# Controller_V1_1.net
KiCad netlist of a schematic drawn in EAGLE
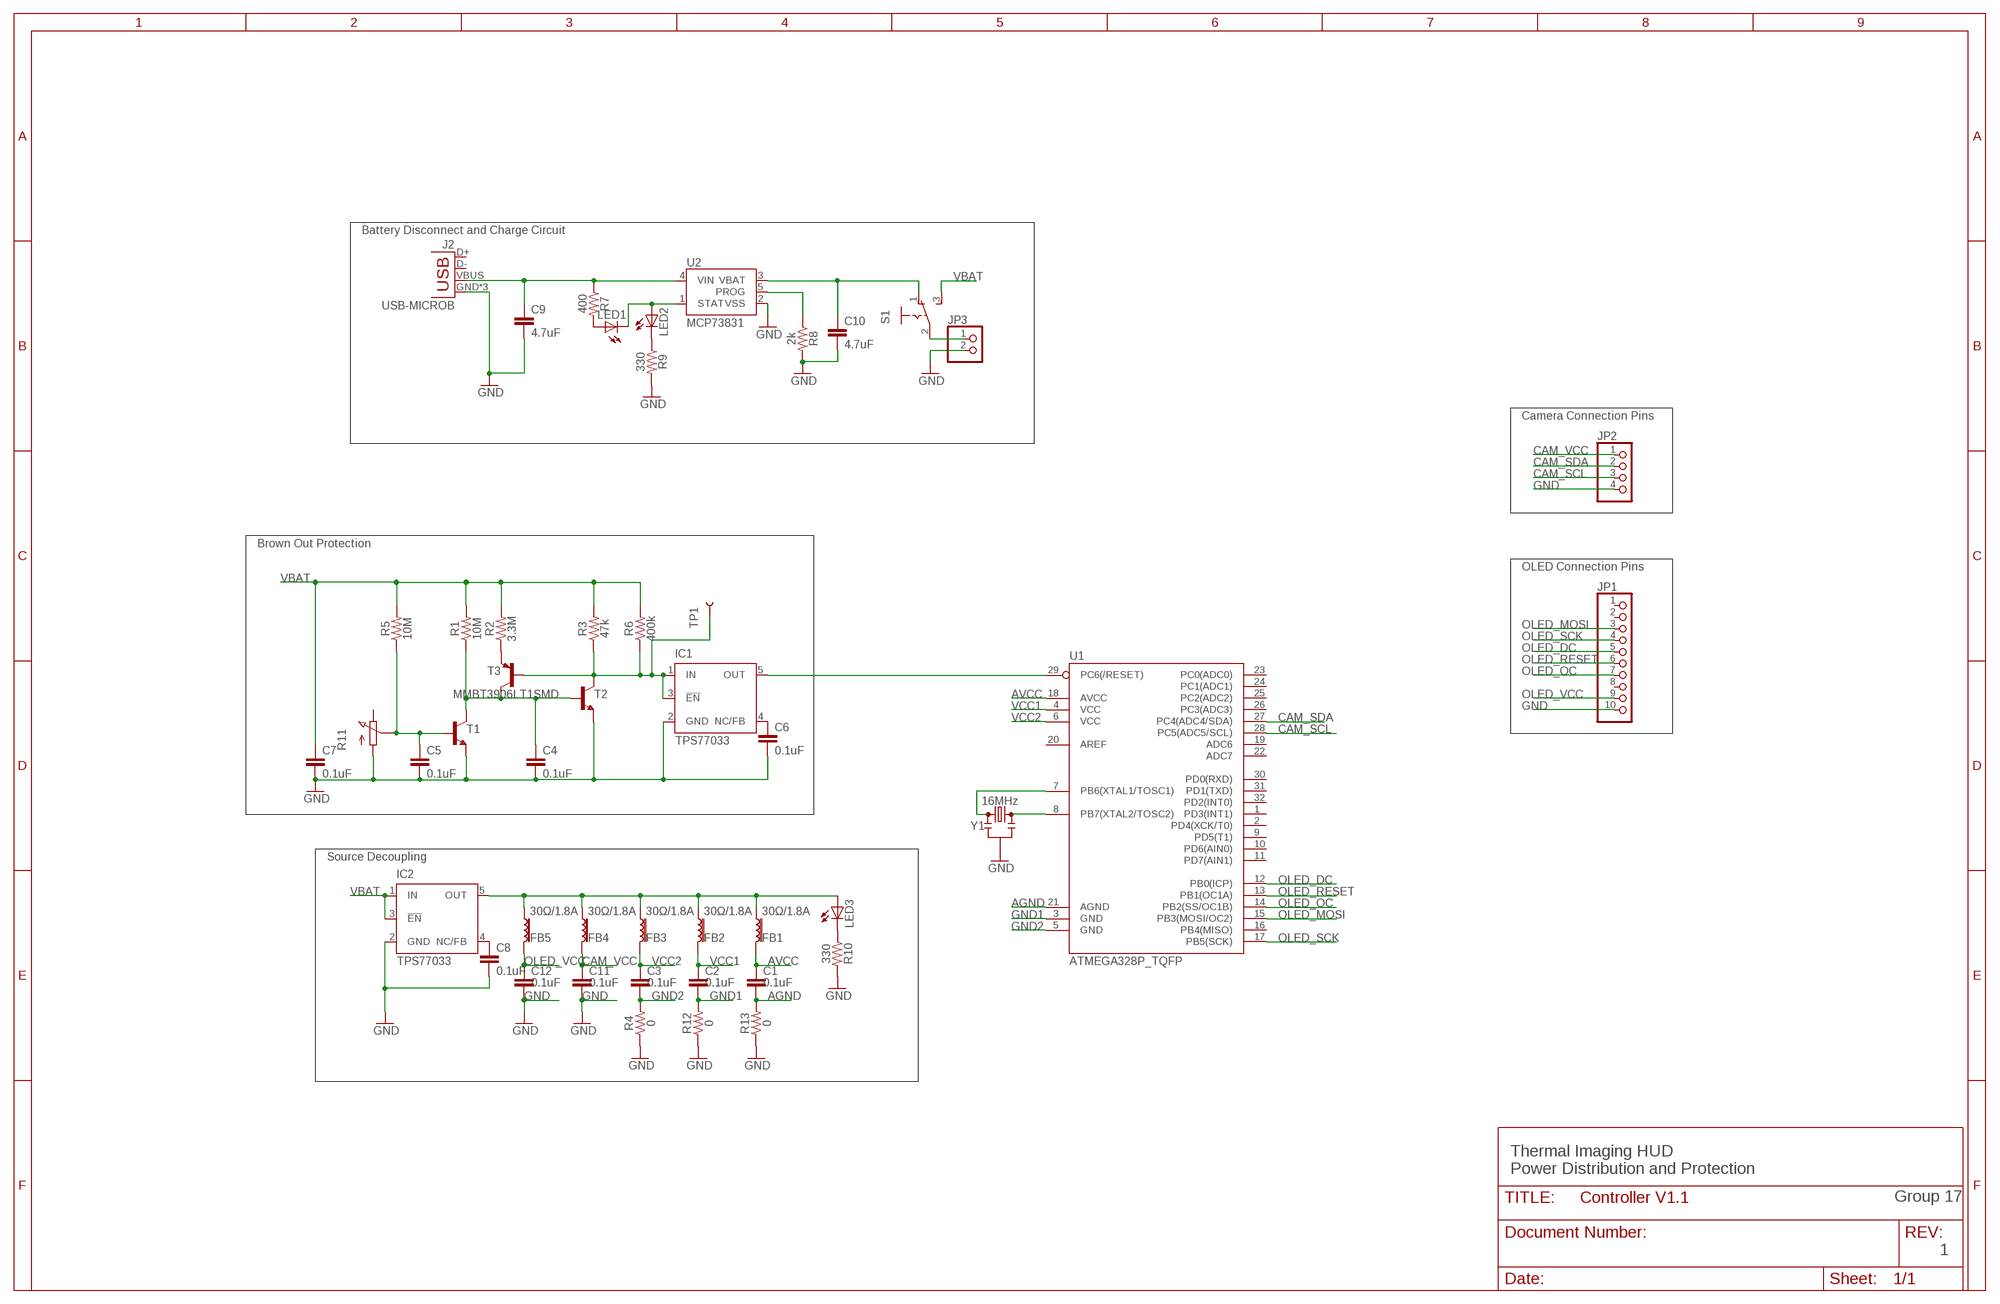
[diagram p0: schematic, sheet 1]

(export (version "E")
  (design (tool "Eeschema 10.0.6"))
  (components
    (comp (ref "C1")
      (value "0.1uF")
      (footprint "eagle-import:0603")
      (libsource (lib "eagle-import") (part "0.1UF-0603-25V-5%"))
    )
    (comp (ref "C2")
      (value "0.1uF")
      (footprint "eagle-import:0603")
      (libsource (lib "eagle-import") (part "0.1UF-0603-25V-5%"))
    )
    (comp (ref "C3")
      (value "0.1uF")
      (footprint "eagle-import:0603")
      (libsource (lib "eagle-import") (part "0.1UF-0603-25V-5%"))
    )
    (comp (ref "C4")
      (value "0.1uF")
      (footprint "eagle-import:0603")
      (libsource (lib "eagle-import") (part "0.1UF-0603-25V-5%"))
    )
    (comp (ref "C5")
      (value "0.1uF")
      (footprint "eagle-import:0603")
      (libsource (lib "eagle-import") (part "0.1UF-0603-25V-5%"))
    )
    (comp (ref "C6")
      (value "0.1uF")
      (footprint "eagle-import:0603")
      (libsource (lib "eagle-import") (part "0.1UF-0603-25V-5%"))
    )
    (comp (ref "C7")
      (value "0.1uF")
      (footprint "eagle-import:0603")
      (libsource (lib "eagle-import") (part "0.1UF-0603-25V-5%"))
    )
    (comp (ref "C8")
      (value "0.1uF")
      (footprint "eagle-import:0603")
      (libsource (lib "eagle-import") (part "0.1UF-0603-25V-5%"))
    )
    (comp (ref "C9")
      (value "4.7uF")
      (footprint "eagle-import:0603")
      (libsource (lib "eagle-import") (part "0.1UF-0603-25V-5%"))
    )
    (comp (ref "C10")
      (value "4.7uF")
      (footprint "eagle-import:0603")
      (libsource (lib "eagle-import") (part "0.1UF-0603-25V-5%"))
    )
    (comp (ref "C11")
      (value "0.1uF")
      (footprint "eagle-import:0603")
      (libsource (lib "eagle-import") (part "0.1UF-0603-25V-5%"))
    )
    (comp (ref "C12")
      (value "0.1uF")
      (footprint "eagle-import:0603")
      (libsource (lib "eagle-import") (part "0.1UF-0603-25V-5%"))
    )
    (comp (ref "FB1")
      (value "30Ω/1.8A")
      (footprint "eagle-import:0603")
      (libsource (lib "eagle-import") (part "FERRITE_BEAD-0603"))
    )
    (comp (ref "FB2")
      (value "30Ω/1.8A")
      (footprint "eagle-import:0603")
      (libsource (lib "eagle-import") (part "FERRITE_BEAD-0603"))
    )
    (comp (ref "FB3")
      (value "30Ω/1.8A")
      (footprint "eagle-import:0603")
      (libsource (lib "eagle-import") (part "FERRITE_BEAD-0603"))
    )
    (comp (ref "FB4")
      (value "30Ω/1.8A")
      (footprint "eagle-import:0603")
      (libsource (lib "eagle-import") (part "FERRITE_BEAD-0603"))
    )
    (comp (ref "FB5")
      (value "30Ω/1.8A")
      (footprint "eagle-import:0603")
      (libsource (lib "eagle-import") (part "FERRITE_BEAD-0603"))
    )
    (comp (ref "IC1")
      (value "TPS77033")
      (footprint "eagle-import:SOT23-DBV")
      (fields (field (name "MF") "TEXAS INSTRUMENTS") (field (name "MPN") "TPS77033DBVT"))
      (libsource (lib "eagle-import") (part "TPS77033"))
    )
    (comp (ref "IC2")
      (value "TPS77033")
      (footprint "eagle-import:SOT23-DBV")
      (fields (field (name "MF") "TEXAS INSTRUMENTS") (field (name "MPN") "TPS77033DBVT"))
      (libsource (lib "eagle-import") (part "TPS77033"))
    )
    (comp (ref "J2")
      (value "USB-MICROB")
      (footprint "eagle-import:USB-MICROB")
      (libsource (lib "eagle-import") (part "USB-MICROB"))
    )
    (comp (ref "JP1")
      (value "PINHD-1X10/90")
      (footprint "eagle-import:1X10_90")
      (libsource (lib "eagle-import") (part "PINHD-1X10/90"))
    )
    (comp (ref "JP2")
      (value "PINHD-1X4/90")
      (footprint "eagle-import:1X04_90")
      (libsource (lib "eagle-import") (part "PINHD-1X4/90"))
    )
    (comp (ref "JP3")
      (value "PINHD-1X2/90")
      (footprint "eagle-import:1X02_90")
      (libsource (lib "eagle-import") (part "PINHD-1X2/90"))
    )
    (comp (ref "LED1")
      (value "LS_T679-D2E2-1")
      (footprint "eagle-import:PLCC2")
      (libsource (lib "eagle-import") (part "_T679-?-1D2E2LS"))
    )
    (comp (ref "LED2")
      (value "LG_T679-E1F1-1")
      (footprint "eagle-import:PLCC2")
      (libsource (lib "eagle-import") (part "_T679-?-1E1F1LG"))
    )
    (comp (ref "LED3")
      (value "LG_T679-E1F1-1")
      (footprint "eagle-import:PLCC2")
      (libsource (lib "eagle-import") (part "_T679-?-1E1F1LG"))
    )
    (comp (ref "R1")
      (value "10M")
      (footprint "eagle-import:0603")
      (libsource (lib "eagle-import") (part "10MOHM-0603-1/10W-5%"))
    )
    (comp (ref "R2")
      (value "3.3M")
      (footprint "eagle-import:0603")
      (libsource (lib "eagle-import") (part "10MOHM-0603-1/10W-5%"))
    )
    (comp (ref "R3")
      (value "47k")
      (footprint "eagle-import:0603")
      (libsource (lib "eagle-import") (part "10MOHM-0603-1/10W-5%"))
    )
    (comp (ref "R4")
      (value "0")
      (footprint "eagle-import:0603")
      (libsource (lib "eagle-import") (part "0OHM-0603-1/10W-5%"))
    )
    (comp (ref "R5")
      (value "10M")
      (footprint "eagle-import:0603")
      (libsource (lib "eagle-import") (part "10MOHM-0603-1/10W-5%"))
    )
    (comp (ref "R6")
      (value "400k")
      (footprint "eagle-import:0603")
      (libsource (lib "eagle-import") (part "10MOHM-0603-1/10W-5%"))
    )
    (comp (ref "R7")
      (value "400")
      (footprint "eagle-import:0603")
      (libsource (lib "eagle-import") (part "10MOHM-0603-1/10W-5%"))
    )
    (comp (ref "R8")
      (value "2k")
      (footprint "eagle-import:0603")
      (libsource (lib "eagle-import") (part "10MOHM-0603-1/10W-5%"))
    )
    (comp (ref "R9")
      (value "330")
      (footprint "eagle-import:0603")
      (libsource (lib "eagle-import") (part "10MOHM-0603-1/10W-5%"))
    )
    (comp (ref "R10")
      (value "330")
      (footprint "eagle-import:0603")
      (libsource (lib "eagle-import") (part "10MOHM-0603-1/10W-5%"))
    )
    (comp (ref "R11")
      (value "PC25")
      (footprint "eagle-import:PC25")
      (fields (field (name "MF") "CLAROSTAT") (field (name "MPN") "308NPC25KS"))
      (libsource (lib "eagle-import") (part "PC25"))
    )
    (comp (ref "R12")
      (value "0")
      (footprint "eagle-import:0603")
      (libsource (lib "eagle-import") (part "0OHM-0603-1/10W-5%"))
    )
    (comp (ref "R13")
      (value "0")
      (footprint "eagle-import:0603")
      (libsource (lib "eagle-import") (part "0OHM-0603-1/10W-5%"))
    )
    (comp (ref "S1")
      (value "255SB")
      (footprint "eagle-import:255SB")
      (libsource (lib "eagle-import") (part "255SB"))
    )
    (comp (ref "T1")
      (value "MMBT3904LT1-NPN-SOT23-BEC")
      (footprint "eagle-import:SOT23-BEC")
      (libsource (lib "eagle-import") (part "-NPN-SOT23-BECMMBT3904LT1"))
    )
    (comp (ref "T2")
      (value "MMBT3904LT1-NPN-SOT23-BEC")
      (footprint "eagle-import:SOT23-BEC")
      (libsource (lib "eagle-import") (part "-NPN-SOT23-BECMMBT3904LT1"))
    )
    (comp (ref "T3")
      (value "MMBT3906LT1SMD")
      (footprint "eagle-import:SOT23-BEC")
      (libsource (lib "eagle-import") (part "MMBT3906SMDLT1"))
    )
    (comp (ref "TP1")
      (value "TEST-POINT3X5")
      (footprint "eagle-import:PAD.03X.05")
      (libsource (lib "eagle-import") (part "TEST-POINT3X5"))
    )
    (comp (ref "U1")
      (value "ATMEGA328P_TQFP")
      (footprint "eagle-import:TQFP32-08")
      (libsource (lib "eagle-import") (part "ATMEGA328P_TQFP"))
    )
    (comp (ref "U2")
      (value "MCP73831")
      (footprint "eagle-import:SOT23-5")
      (libsource (lib "eagle-import") (part "MCP73831"))
    )
    (comp (ref "Y1")
      (value "16MHz")
      (footprint "eagle-import:RESONATOR-SMD-3.2X1.3")
      (libsource (lib "eagle-import") (part "RESONATOR-16MHZSMD_3.2X1.3"))
    )
  )
  (nets
    (net (code "1") (name "/AGND") (class "Default")
      (node (ref "C1") (pin "2") (pinfunction "2_2") (pintype "passive"))
      (node (ref "R13") (pin "2") (pinfunction "2_2") (pintype "passive"))
      (node (ref "U1") (pin "21") (pinfunction "AGND_21") (pintype "bidirectional"))
    )
    (net (code "2") (name "/AVCC") (class "Default")
      (node (ref "C1") (pin "1") (pinfunction "1_1") (pintype "passive"))
      (node (ref "FB1") (pin "2") (pinfunction "2_2") (pintype "passive"))
      (node (ref "U1") (pin "18") (pinfunction "AVCC_18") (pintype "bidirectional"))
    )
    (net (code "3") (name "/CAM_SCL") (class "Default")
      (node (ref "JP2") (pin "3") (pinfunction "3_3") (pintype "passive"))
      (node (ref "U1") (pin "28") (pinfunction "PC5(ADC5/SCL)_28") (pintype "bidirectional"))
    )
    (net (code "4") (name "/CAM_SDA") (class "Default")
      (node (ref "JP2") (pin "2") (pinfunction "2_2") (pintype "passive"))
      (node (ref "U1") (pin "27") (pinfunction "PC4(ADC4/SDA)_27") (pintype "bidirectional"))
    )
    (net (code "5") (name "/CAM_VCC") (class "Default")
      (node (ref "C11") (pin "1") (pinfunction "1_1") (pintype "passive"))
      (node (ref "FB4") (pin "2") (pinfunction "2_2") (pintype "passive"))
      (node (ref "JP2") (pin "1") (pinfunction "1_1") (pintype "passive"))
    )
    (net (code "6") (name "/GND1") (class "Default")
      (node (ref "C2") (pin "2") (pinfunction "2_2") (pintype "passive"))
      (node (ref "R12") (pin "2") (pinfunction "2_2") (pintype "passive"))
      (node (ref "U1") (pin "3") (pinfunction "GND_3") (pintype "bidirectional"))
    )
    (net (code "7") (name "/GND2") (class "Default")
      (node (ref "C3") (pin "2") (pinfunction "2_2") (pintype "passive"))
      (node (ref "R4") (pin "2") (pinfunction "2_2") (pintype "passive"))
      (node (ref "U1") (pin "5") (pinfunction "GND_5") (pintype "bidirectional"))
    )
    (net (code "8") (name "/OLED_DC") (class "Default")
      (node (ref "JP1") (pin "5") (pinfunction "5_5") (pintype "passive"))
      (node (ref "U1") (pin "12") (pinfunction "PB0(ICP)_12") (pintype "bidirectional"))
    )
    (net (code "9") (name "/OLED_MOSI") (class "Default")
      (node (ref "JP1") (pin "3") (pinfunction "3_3") (pintype "passive"))
      (node (ref "U1") (pin "15") (pinfunction "PB3(MOSI/OC2)_15") (pintype "bidirectional"))
    )
    (net (code "10") (name "/OLED_OC") (class "Default")
      (node (ref "JP1") (pin "7") (pinfunction "7_7") (pintype "passive"))
      (node (ref "U1") (pin "14") (pinfunction "PB2(SS/OC1B)_14") (pintype "bidirectional"))
    )
    (net (code "11") (name "/OLED_RESET") (class "Default")
      (node (ref "JP1") (pin "6") (pinfunction "6_6") (pintype "passive"))
      (node (ref "U1") (pin "13") (pinfunction "PB1(OC1A)_13") (pintype "bidirectional"))
    )
    (net (code "12") (name "/OLED_SCK") (class "Default")
      (node (ref "JP1") (pin "4") (pinfunction "4_4") (pintype "passive"))
      (node (ref "U1") (pin "17") (pinfunction "PB5(SCK)_17") (pintype "bidirectional"))
    )
    (net (code "13") (name "/OLED_VCC") (class "Default")
      (node (ref "C12") (pin "1") (pinfunction "1_1") (pintype "passive"))
      (node (ref "FB5") (pin "2") (pinfunction "2_2") (pintype "passive"))
      (node (ref "JP1") (pin "9") (pinfunction "9_9") (pintype "passive"))
    )
    (net (code "14") (name "/VBAT") (class "Default")
      (node (ref "C7") (pin "1") (pinfunction "1_1") (pintype "passive"))
      (node (ref "IC2") (pin "1") (pinfunction "IN_1") (pintype "input"))
      (node (ref "IC2") (pin "3") (pinfunction "~{EN}_3") (pintype "input"))
      (node (ref "R1") (pin "2") (pinfunction "2_2") (pintype "passive"))
      (node (ref "R2") (pin "2") (pinfunction "2_2") (pintype "passive"))
      (node (ref "R3") (pin "2") (pinfunction "2_2") (pintype "passive"))
      (node (ref "R5") (pin "2") (pinfunction "2_2") (pintype "passive"))
      (node (ref "R6") (pin "2") (pinfunction "2_2") (pintype "passive"))
      (node (ref "S1") (pin "3") (pinfunction "S_3") (pintype "passive"))
    )
    (net (code "15") (name "/VCC1") (class "Default")
      (node (ref "C2") (pin "1") (pinfunction "1_1") (pintype "passive"))
      (node (ref "FB2") (pin "2") (pinfunction "2_2") (pintype "passive"))
      (node (ref "U1") (pin "4") (pinfunction "VCC_4") (pintype "bidirectional"))
    )
    (net (code "16") (name "/VCC2") (class "Default")
      (node (ref "C3") (pin "1") (pinfunction "1_1") (pintype "passive"))
      (node (ref "FB3") (pin "2") (pinfunction "2_2") (pintype "passive"))
      (node (ref "U1") (pin "6") (pinfunction "VCC_6") (pintype "bidirectional"))
    )
    (net (code "17") (name "GND") (class "Default")
      (node (ref "C10") (pin "2") (pinfunction "2_2") (pintype "passive"))
      (node (ref "C11") (pin "2") (pinfunction "2_2") (pintype "passive"))
      (node (ref "C12") (pin "2") (pinfunction "2_2") (pintype "passive"))
      (node (ref "C4") (pin "2") (pinfunction "2_2") (pintype "passive"))
      (node (ref "C5") (pin "2") (pinfunction "2_2") (pintype "passive"))
      (node (ref "C6") (pin "2") (pinfunction "2_2") (pintype "passive"))
      (node (ref "C7") (pin "2") (pinfunction "2_2") (pintype "passive"))
      (node (ref "C8") (pin "2") (pinfunction "2_2") (pintype "passive"))
      (node (ref "C9") (pin "2") (pinfunction "2_2") (pintype "passive"))
      (node (ref "IC1") (pin "2") (pinfunction "GND_2") (pintype "power_in"))
      (node (ref "IC2") (pin "2") (pinfunction "GND_2") (pintype "power_in"))
      (node (ref "J2") (pin "GND") (pinfunction "GND_GND") (pintype "bidirectional"))
      (node (ref "J2") (pin "MT1") (pinfunction "GND_MT1") (pintype "bidirectional"))
      (node (ref "J2") (pin "MT2") (pinfunction "GND_MT2") (pintype "bidirectional"))
      (node (ref "JP1") (pin "10") (pinfunction "10_10") (pintype "passive"))
      (node (ref "JP2") (pin "4") (pinfunction "4_4") (pintype "passive"))
      (node (ref "JP3") (pin "2") (pinfunction "2_2") (pintype "passive"))
      (node (ref "R10") (pin "2") (pinfunction "2_2") (pintype "passive"))
      (node (ref "R11") (pin "A") (pinfunction "A_A") (pintype "passive"))
      (node (ref "R12") (pin "1") (pinfunction "1_1") (pintype "passive"))
      (node (ref "R13") (pin "1") (pinfunction "1_1") (pintype "passive"))
      (node (ref "R4") (pin "1") (pinfunction "1_1") (pintype "passive"))
      (node (ref "R8") (pin "2") (pinfunction "2_2") (pintype "passive"))
      (node (ref "R9") (pin "2") (pinfunction "2_2") (pintype "passive"))
      (node (ref "T1") (pin "E") (pinfunction "E_E") (pintype "passive"))
      (node (ref "T2") (pin "E") (pinfunction "E_E") (pintype "passive"))
      (node (ref "U2") (pin "2") (pinfunction "VSS_2") (pintype "power_in"))
      (node (ref "Y1") (pin "2") (pinfunction "2_2") (pintype "passive"))
    )
    (net (code "18") (name "Net-(C4-Pad1)") (class "Default")
      (node (ref "C4") (pin "1") (pinfunction "1_1") (pintype "passive"))
      (node (ref "R1") (pin "1") (pinfunction "1_1") (pintype "passive"))
      (node (ref "T1") (pin "C") (pinfunction "C_C") (pintype "passive"))
      (node (ref "T2") (pin "B") (pinfunction "B_B") (pintype "passive"))
      (node (ref "T3") (pin "C") (pinfunction "C_C") (pintype "passive"))
    )
    (net (code "19") (name "Net-(C5-Pad1)") (class "Default")
      (node (ref "C5") (pin "1") (pinfunction "1_1") (pintype "passive"))
      (node (ref "R11") (pin "S") (pinfunction "S_S") (pintype "passive"))
      (node (ref "R5") (pin "1") (pinfunction "1_1") (pintype "passive"))
      (node (ref "T1") (pin "B") (pinfunction "B_B") (pintype "passive"))
    )
    (net (code "20") (name "Net-(IC1-IN)") (class "Default")
      (node (ref "IC1") (pin "1") (pinfunction "IN_1") (pintype "input"))
      (node (ref "IC1") (pin "3") (pinfunction "~{EN}_3") (pintype "input"))
      (node (ref "R3") (pin "1") (pinfunction "1_1") (pintype "passive"))
      (node (ref "R6") (pin "1") (pinfunction "1_1") (pintype "passive"))
      (node (ref "T2") (pin "C") (pinfunction "C_C") (pintype "passive"))
      (node (ref "T3") (pin "B") (pinfunction "B_B") (pintype "passive"))
      (node (ref "TP1") (pin "P$1") (pinfunction "1_P$1") (pintype "bidirectional"))
    )
    (net (code "21") (name "Net-(IC1-NC{slash}FB)") (class "Default")
      (node (ref "C6") (pin "1") (pinfunction "1_1") (pintype "passive"))
      (node (ref "IC1") (pin "4") (pinfunction "NC/FB_4") (pintype "passive"))
    )
    (net (code "22") (name "Net-(IC1-OUT)") (class "Default")
      (node (ref "IC1") (pin "5") (pinfunction "OUT_5") (pintype "passive"))
      (node (ref "U1") (pin "29") (pinfunction "PC6(/RESET)_29") (pintype "bidirectional"))
    )
    (net (code "23") (name "Net-(IC2-NC{slash}FB)") (class "Default")
      (node (ref "C8") (pin "1") (pinfunction "1_1") (pintype "passive"))
      (node (ref "IC2") (pin "4") (pinfunction "NC/FB_4") (pintype "passive"))
    )
    (net (code "24") (name "Net-(IC2-OUT)") (class "Default")
      (node (ref "FB1") (pin "1") (pinfunction "1_1") (pintype "passive"))
      (node (ref "FB2") (pin "1") (pinfunction "1_1") (pintype "passive"))
      (node (ref "FB3") (pin "1") (pinfunction "1_1") (pintype "passive"))
      (node (ref "FB4") (pin "1") (pinfunction "1_1") (pintype "passive"))
      (node (ref "FB5") (pin "1") (pinfunction "1_1") (pintype "passive"))
      (node (ref "IC2") (pin "5") (pinfunction "OUT_5") (pintype "passive"))
      (node (ref "LED3") (pin "A") (pinfunction "A_A") (pintype "passive"))
    )
    (net (code "25") (name "Net-(LED1-PadA)") (class "Default")
      (node (ref "LED1") (pin "A") (pinfunction "A_A") (pintype "passive"))
      (node (ref "R7") (pin "2") (pinfunction "2_2") (pintype "passive"))
    )
    (net (code "26") (name "Net-(LED2-PadC)") (class "Default")
      (node (ref "LED2") (pin "C") (pinfunction "C_C") (pintype "passive"))
      (node (ref "R9") (pin "1") (pinfunction "1_1") (pintype "passive"))
    )
    (net (code "27") (name "Net-(LED3-PadC)") (class "Default")
      (node (ref "LED3") (pin "C") (pinfunction "C_C") (pintype "passive"))
      (node (ref "R10") (pin "1") (pinfunction "1_1") (pintype "passive"))
    )
    (net (code "28") (name "Net-(R2-Pad1)") (class "Default")
      (node (ref "R2") (pin "1") (pinfunction "1_1") (pintype "passive"))
      (node (ref "T3") (pin "E") (pinfunction "E_E") (pintype "passive"))
    )
    (net (code "29") (name "Net-(S1-O)") (class "Default")
      (node (ref "C10") (pin "1") (pinfunction "1_1") (pintype "passive"))
      (node (ref "S1") (pin "1") (pinfunction "O_1") (pintype "passive"))
      (node (ref "U2") (pin "3") (pinfunction "VBAT_3") (pintype "power_in"))
    )
    (net (code "30") (name "Net-(S1-P)") (class "Default")
      (node (ref "JP3") (pin "1") (pinfunction "1_1") (pintype "passive"))
      (node (ref "S1") (pin "2") (pinfunction "P_2") (pintype "passive"))
    )
    (net (code "31") (name "Net-(U1-PB6(XTAL1{slash}TOSC1))") (class "Default")
      (node (ref "U1") (pin "7") (pinfunction "PB6(XTAL1/TOSC1)_7") (pintype "bidirectional"))
      (node (ref "Y1") (pin "1") (pinfunction "1_1") (pintype "passive"))
    )
    (net (code "32") (name "Net-(U1-PB7(XTAL2{slash}TOSC2))") (class "Default")
      (node (ref "U1") (pin "8") (pinfunction "PB7(XTAL2/TOSC2)_8") (pintype "bidirectional"))
      (node (ref "Y1") (pin "3") (pinfunction "3_3") (pintype "passive"))
    )
    (net (code "33") (name "Net-(U2-PROG)") (class "Default")
      (node (ref "R8") (pin "1") (pinfunction "1_1") (pintype "passive"))
      (node (ref "U2") (pin "5") (pinfunction "PROG_5") (pintype "input"))
    )
    (net (code "34") (name "Net-(U2-STAT)") (class "Default")
      (node (ref "LED1") (pin "C") (pinfunction "C_C") (pintype "passive"))
      (node (ref "LED2") (pin "A") (pinfunction "A_A") (pintype "passive"))
      (node (ref "U2") (pin "1") (pinfunction "STAT_1") (pintype "output"))
    )
    (net (code "35") (name "Net-(U2-VIN)") (class "Default")
      (node (ref "C9") (pin "1") (pinfunction "1_1") (pintype "passive"))
      (node (ref "J2") (pin "VBUS") (pinfunction "VBUS_VBUS") (pintype "bidirectional"))
      (node (ref "R7") (pin "1") (pinfunction "1_1") (pintype "passive"))
      (node (ref "U2") (pin "4") (pinfunction "VIN_4") (pintype "power_in"))
    )
    (net (code "36") (name "unconnected-(J2-PadD+)") (class "Default")
      (node (ref "J2") (pin "D+") (pinfunction "D+_D+") (pintype "bidirectional"))
    )
    (net (code "37") (name "unconnected-(J2-PadD-)") (class "Default")
      (node (ref "J2") (pin "D-") (pinfunction "D-_D-") (pintype "bidirectional"))
    )
    (net (code "38") (name "unconnected-(JP1-Pad1)") (class "Default")
      (node (ref "JP1") (pin "1") (pinfunction "1_1") (pintype "passive"))
    )
    (net (code "39") (name "unconnected-(JP1-Pad2)") (class "Default")
      (node (ref "JP1") (pin "2") (pinfunction "2_2") (pintype "passive"))
    )
    (net (code "40") (name "unconnected-(JP1-Pad8)") (class "Default")
      (node (ref "JP1") (pin "8") (pinfunction "8_8") (pintype "passive"))
    )
    (net (code "41") (name "unconnected-(R11-PadE)") (class "Default")
      (node (ref "R11") (pin "E") (pinfunction "E_E") (pintype "passive"))
    )
    (net (code "42") (name "unconnected-(U1-ADC6-Pad19)") (class "Default")
      (node (ref "U1") (pin "19") (pinfunction "ADC6_19") (pintype "bidirectional"))
    )
    (net (code "43") (name "unconnected-(U1-ADC7-Pad22)") (class "Default")
      (node (ref "U1") (pin "22") (pinfunction "ADC7_22") (pintype "bidirectional"))
    )
    (net (code "44") (name "unconnected-(U1-AREF-Pad20)") (class "Default")
      (node (ref "U1") (pin "20") (pinfunction "AREF_20") (pintype "bidirectional"))
    )
    (net (code "45") (name "unconnected-(U1-PB4(MISO)-Pad16)") (class "Default")
      (node (ref "U1") (pin "16") (pinfunction "PB4(MISO)_16") (pintype "bidirectional"))
    )
    (net (code "46") (name "unconnected-(U1-PC0(ADC0)-Pad23)") (class "Default")
      (node (ref "U1") (pin "23") (pinfunction "PC0(ADC0)_23") (pintype "bidirectional"))
    )
    (net (code "47") (name "unconnected-(U1-PC1(ADC1)-Pad24)") (class "Default")
      (node (ref "U1") (pin "24") (pinfunction "PC1(ADC1)_24") (pintype "bidirectional"))
    )
    (net (code "48") (name "unconnected-(U1-PC2(ADC2)-Pad25)") (class "Default")
      (node (ref "U1") (pin "25") (pinfunction "PC2(ADC2)_25") (pintype "bidirectional"))
    )
    (net (code "49") (name "unconnected-(U1-PC3(ADC3)-Pad26)") (class "Default")
      (node (ref "U1") (pin "26") (pinfunction "PC3(ADC3)_26") (pintype "bidirectional"))
    )
    (net (code "50") (name "unconnected-(U1-PD0(RXD)-Pad30)") (class "Default")
      (node (ref "U1") (pin "30") (pinfunction "PD0(RXD)_30") (pintype "bidirectional"))
    )
    (net (code "51") (name "unconnected-(U1-PD1(TXD)-Pad31)") (class "Default")
      (node (ref "U1") (pin "31") (pinfunction "PD1(TXD)_31") (pintype "bidirectional"))
    )
    (net (code "52") (name "unconnected-(U1-PD2(INT0)-Pad32)") (class "Default")
      (node (ref "U1") (pin "32") (pinfunction "PD2(INT0)_32") (pintype "bidirectional"))
    )
    (net (code "53") (name "unconnected-(U1-PD3(INT1)-Pad1)") (class "Default")
      (node (ref "U1") (pin "1") (pinfunction "PD3(INT1)_1") (pintype "bidirectional"))
    )
    (net (code "54") (name "unconnected-(U1-PD4(XCK{slash}T0)-Pad2)") (class "Default")
      (node (ref "U1") (pin "2") (pinfunction "PD4(XCK/T0)_2") (pintype "bidirectional"))
    )
    (net (code "55") (name "unconnected-(U1-PD5(T1)-Pad9)") (class "Default")
      (node (ref "U1") (pin "9") (pinfunction "PD5(T1)_9") (pintype "bidirectional"))
    )
    (net (code "56") (name "unconnected-(U1-PD6(AIN0)-Pad10)") (class "Default")
      (node (ref "U1") (pin "10") (pinfunction "PD6(AIN0)_10") (pintype "bidirectional"))
    )
    (net (code "57") (name "unconnected-(U1-PD7(AIN1)-Pad11)") (class "Default")
      (node (ref "U1") (pin "11") (pinfunction "PD7(AIN1)_11") (pintype "bidirectional"))
    )
  )
)
